# Tracksoar_v1_2_active_gps.net
KiCad netlist of a schematic drawn in EAGLE
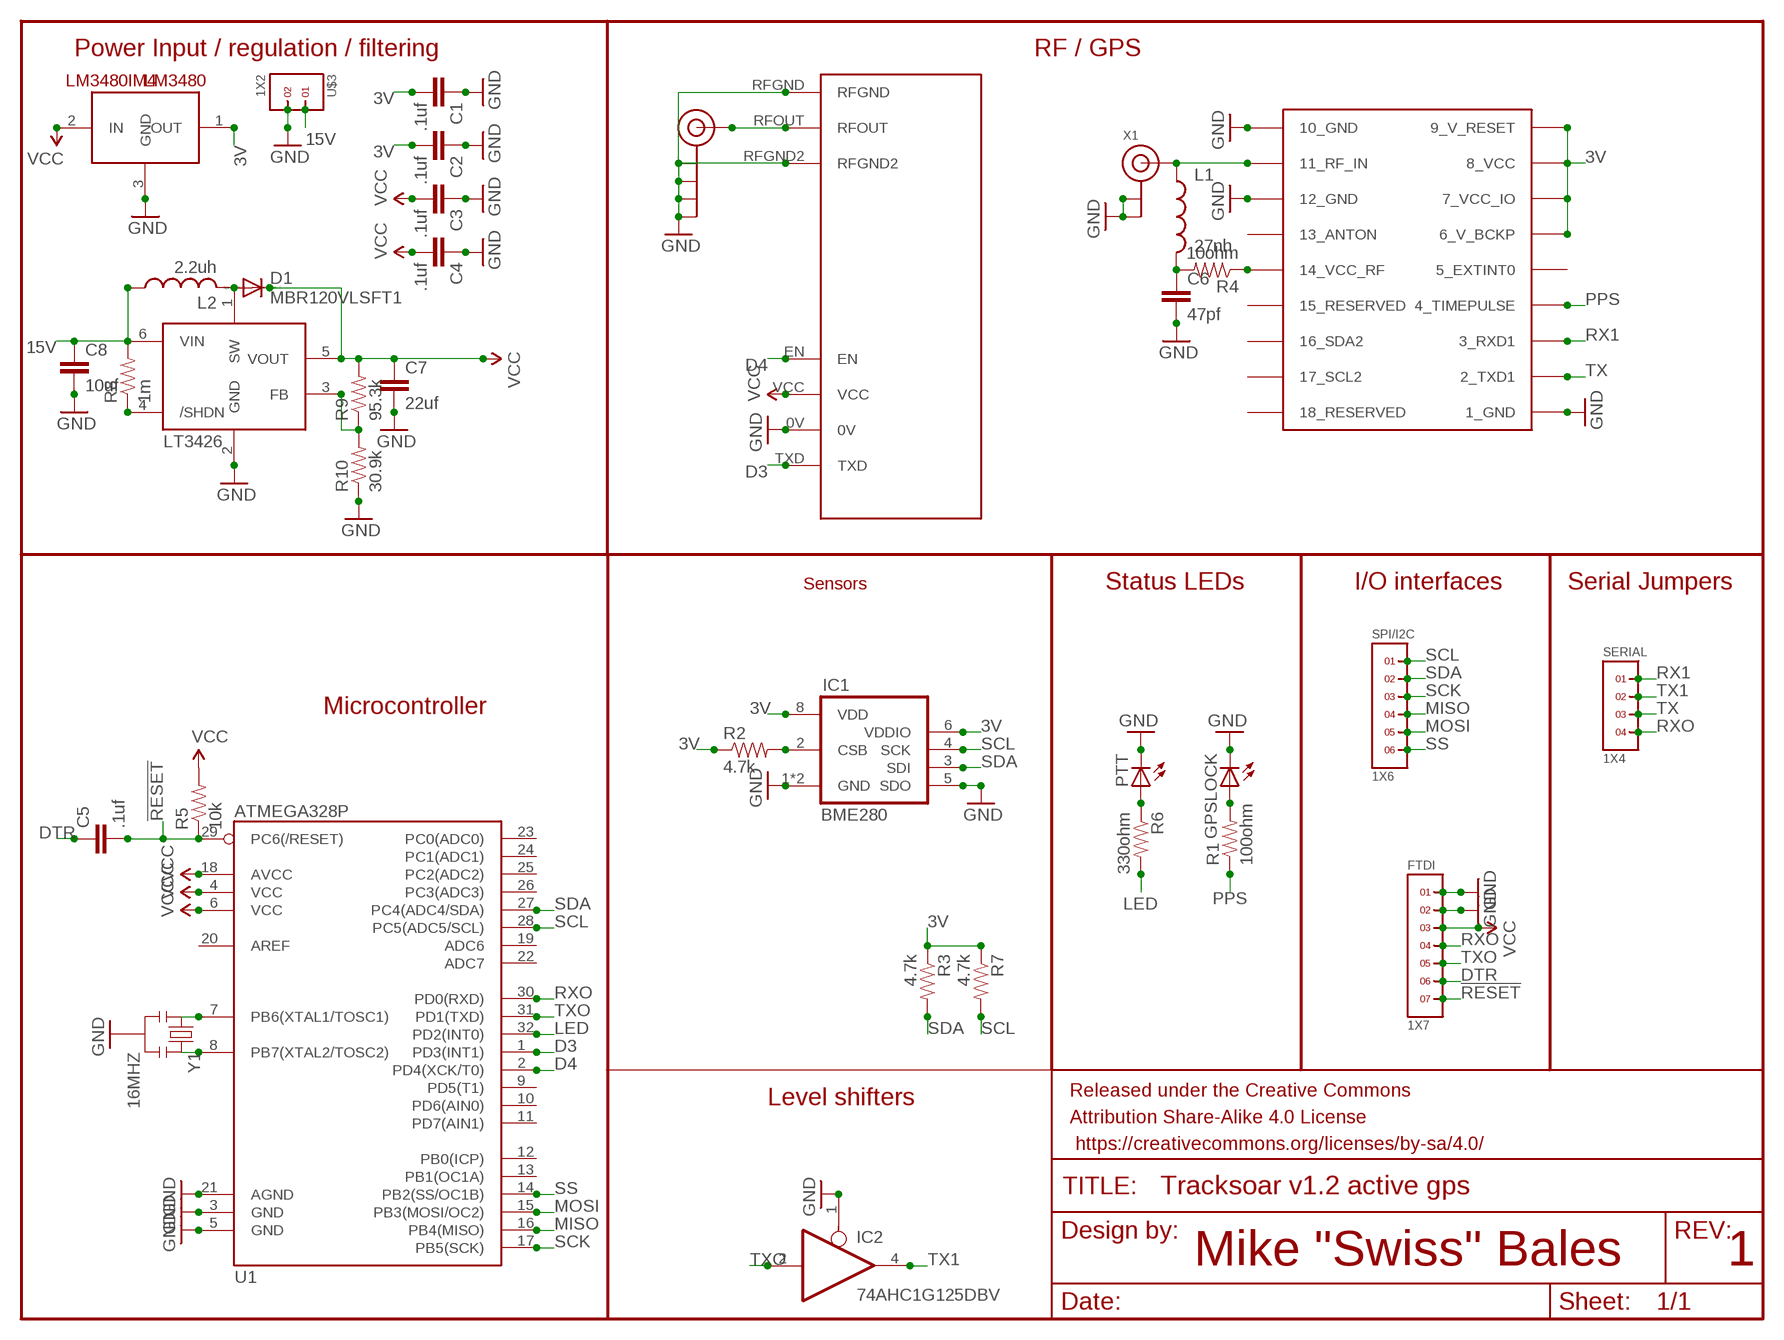
[diagram p0: schematic, sheet 1]

(export (version "E")
  (design (tool "Eeschema 10.0.6"))
  (components
    (comp (ref "C1")
      (value ".1uf")
      (footprint "eagle-import:0805")
      (libsource (lib "eagle-import") (part "CAP0805"))
    )
    (comp (ref "C2")
      (value ".1uf")
      (footprint "eagle-import:0805")
      (libsource (lib "eagle-import") (part "CAP0805"))
    )
    (comp (ref "C3")
      (value ".1uf")
      (footprint "eagle-import:0805")
      (libsource (lib "eagle-import") (part "CAP0805"))
    )
    (comp (ref "C4")
      (value ".1uf")
      (footprint "eagle-import:0805")
      (libsource (lib "eagle-import") (part "CAP0805"))
    )
    (comp (ref "C5")
      (value ".1uf")
      (footprint "eagle-import:0805")
      (libsource (lib "eagle-import") (part "CAP0805"))
    )
    (comp (ref "C6")
      (value "47pf")
      (footprint "eagle-import:0805")
      (libsource (lib "eagle-import") (part "SparkFun-Passives_CAP0805"))
    )
    (comp (ref "C7")
      (value "22uf")
      (footprint "eagle-import:0805")
      (libsource (lib "eagle-import") (part "CAP0805"))
    )
    (comp (ref "C8")
      (value "10uf")
      (footprint "eagle-import:0805")
      (libsource (lib "eagle-import") (part "CAP0805"))
    )
    (comp (ref "D1")
      (value "MBR120VLSFT1")
      (footprint "eagle-import:SOD123")
      (libsource (lib "eagle-import") (part "DIODE-SOD123"))
    )
    (comp (ref "FRAME1")
      (value "FRAME-LETTER")
      (footprint "eagle-import:CREATIVE_COMMONS")
      (libsource (lib "eagle-import") (part "FRAME-LETTER"))
    )
    (comp (ref "FTDI")
      (value "1X7")
      (footprint "eagle-import:1X7")
      (libsource (lib "eagle-import") (part "1X7"))
    )
    (comp (ref "GPSLOCK")
      (value "LEDCHIP-LED0805")
      (footprint "eagle-import:CHIP-LED0805")
      (libsource (lib "eagle-import") (part "LEDCHIP-LED0805"))
    )
    (comp (ref "IC1")
      (value "BME280")
      (footprint "eagle-import:BME280")
      (libsource (lib "eagle-import") (part "BME280"))
    )
    (comp (ref "IC2")
      (value "74AHC1G125DBV")
      (footprint "eagle-import:SOT23-5")
      (libsource (lib "eagle-import") (part "741G125DBVAHC"))
    )
    (comp (ref "J$1")
      (value "SMA_EDGE")
      (footprint "eagle-import:SMA-EDGE")
      (libsource (lib "eagle-import") (part "SMA_EDGE"))
    )
    (comp (ref "L1")
      (value "27nh")
      (footprint "eagle-import:0805")
      (libsource (lib "eagle-import") (part "INDUCTOR0805"))
    )
    (comp (ref "L2")
      (value "2.2uh")
      (footprint "eagle-import:L1812")
      (libsource (lib "eagle-import") (part "L-USL1812"))
    )
    (comp (ref "LM3480")
      (value "LM3480IM4")
      (footprint "eagle-import:SOT23-3")
      (libsource (lib "eagle-import") (part "LM3480IM4"))
    )
    (comp (ref "LT3426")
      (value "LT3426")
      (footprint "eagle-import:SOT23-6")
      (libsource (lib "eagle-import") (part "LT3426"))
    )
    (comp (ref "PTT")
      (value "LEDCHIP-LED0805")
      (footprint "eagle-import:CHIP-LED0805")
      (libsource (lib "eagle-import") (part "LEDCHIP-LED0805"))
    )
    (comp (ref "R1")
      (value "100ohm")
      (footprint "eagle-import:0805")
      (libsource (lib "eagle-import") (part "SparkFun-Resistors_RESISTOR0805-RES"))
    )
    (comp (ref "R2")
      (value "4.7k")
      (footprint "eagle-import:0805")
      (libsource (lib "eagle-import") (part "SparkFun-Resistors_RESISTOR0805-RES"))
    )
    (comp (ref "R3")
      (value "4.7k")
      (footprint "eagle-import:0805")
      (libsource (lib "eagle-import") (part "SparkFun-Resistors_RESISTOR0805-RES"))
    )
    (comp (ref "R4")
      (value "10ohm")
      (footprint "eagle-import:0805")
      (libsource (lib "eagle-import") (part "RESISTOR0805-RES"))
    )
    (comp (ref "R5")
      (value "10k")
      (footprint "eagle-import:0805")
      (libsource (lib "eagle-import") (part "SparkFun-Resistors_RESISTOR0805-RES"))
    )
    (comp (ref "R6")
      (value "330ohm")
      (footprint "eagle-import:0805")
      (libsource (lib "eagle-import") (part "SparkFun-Resistors_RESISTOR0805-RES"))
    )
    (comp (ref "R7")
      (value "4.7k")
      (footprint "eagle-import:0805")
      (libsource (lib "eagle-import") (part "SparkFun-Resistors_RESISTOR0805-RES"))
    )
    (comp (ref "R8")
      (value "1m")
      (footprint "eagle-import:0805")
      (libsource (lib "eagle-import") (part "SparkFun-Resistors_RESISTOR0805-RES"))
    )
    (comp (ref "R9")
      (value "95.3k")
      (footprint "eagle-import:0805")
      (libsource (lib "eagle-import") (part "SparkFun-Resistors_RESISTOR0805-RES"))
    )
    (comp (ref "R10")
      (value "30.9k")
      (footprint "eagle-import:0805")
      (libsource (lib "eagle-import") (part "SparkFun-Resistors_RESISTOR0805-RES"))
    )
    (comp (ref "SERIAL")
      (value "1X4")
      (footprint "eagle-import:1X4")
      (libsource (lib "eagle-import") (part "1X4"))
    )
    (comp (ref "SPI/I2C")
      (value "1X6")
      (footprint "eagle-import:1X6")
      (libsource (lib "eagle-import") (part "1X6"))
    )
    (comp (ref "U$1")
      (value "UBLOX_MAX")
      (footprint "eagle-import:UBLOX_MAX")
      (libsource (lib "eagle-import") (part "UBLOX_MAX"))
    )
    (comp (ref "U$2")
      (value "RADIOMETRIX-HX1")
      (footprint "eagle-import:RADIOMETRIX-HX1")
      (libsource (lib "eagle-import") (part "RADIOMETRIX-HX1"))
    )
    (comp (ref "U$3")
      (value "1X2")
      (footprint "eagle-import:1X2")
      (libsource (lib "eagle-import") (part "1X2"))
    )
    (comp (ref "U1")
      (value "ATMEGA328P")
      (footprint "eagle-import:MLF32")
      (libsource (lib "eagle-import") (part "ATMEGA168MLF"))
    )
    (comp (ref "X1")
      (value "ANTENNA_U.FL")
      (footprint "eagle-import:U.FL")
      (libsource (lib "eagle-import") (part "ANTENNA_U.FL"))
    )
    (comp (ref "Y1")
      (value "16MHZ")
      (footprint "eagle-import:RESONATOR-SMD")
      (libsource (lib "eagle-import") (part "RESONATOR16MHZ"))
    )
  )
  (nets
    (net (code "1") (name "/3V") (class "Default")
      (node (ref "C1") (pin "2") (pinfunction "2_2") (pintype "passive"))
      (node (ref "C2") (pin "2") (pinfunction "2_2") (pintype "passive"))
      (node (ref "IC1") (pin "6") (pinfunction "VDDIO_6") (pintype "power_in"))
      (node (ref "IC1") (pin "8") (pinfunction "VDD_8") (pintype "power_in"))
      (node (ref "LM3480") (pin "1") (pinfunction "OUT_1") (pintype "bidirectional"))
      (node (ref "R2") (pin "1") (pinfunction "1_1") (pintype "passive"))
      (node (ref "R3") (pin "1") (pinfunction "1_1") (pintype "passive"))
      (node (ref "R7") (pin "1") (pinfunction "1_1") (pintype "passive"))
      (node (ref "U$1") (pin "6_V_BCKP") (pinfunction "6_V_BCKP_6_V_BCKP") (pintype "bidirectional"))
      (node (ref "U$1") (pin "7_VCC_IO") (pinfunction "7_VCC_IO_7_VCC_IO") (pintype "power_in"))
      (node (ref "U$1") (pin "8_VCC") (pinfunction "8_VCC_8_VCC") (pintype "power_in"))
      (node (ref "U$1") (pin "9_V_RESET") (pinfunction "9_V_RESET_9_V_RESET") (pintype "power_in"))
    )
    (net (code "2") (name "/15V") (class "Default")
      (node (ref "C8") (pin "1") (pinfunction "1_1") (pintype "passive"))
      (node (ref "L2") (pin "1") (pinfunction "1_1") (pintype "passive"))
      (node (ref "LT3426") (pin "6") (pinfunction "VIN_6") (pintype "input"))
      (node (ref "R8") (pin "2") (pinfunction "2_2") (pintype "passive"))
      (node (ref "U$3") (pin "1") (pinfunction "1_1") (pintype "bidirectional"))
    )
    (net (code "3") (name "/D3") (class "Default")
      (node (ref "U$2") (pin "TXD") (pinfunction "TXD_TXD") (pintype "bidirectional"))
      (node (ref "U1") (pin "1") (pinfunction "PD3(INT1)_1") (pintype "bidirectional"))
    )
    (net (code "4") (name "/D4") (class "Default")
      (node (ref "U$2") (pin "EN") (pinfunction "EN_EN") (pintype "bidirectional"))
      (node (ref "U1") (pin "2") (pinfunction "PD4(XCK/T0)_2") (pintype "bidirectional"))
    )
    (net (code "5") (name "/DTR") (class "Default")
      (node (ref "C5") (pin "1") (pinfunction "1_1") (pintype "passive"))
      (node (ref "FTDI") (pin "6") (pinfunction "6_6") (pintype "bidirectional"))
    )
    (net (code "6") (name "/LED") (class "Default")
      (node (ref "R6") (pin "2") (pinfunction "2_2") (pintype "passive"))
      (node (ref "U1") (pin "32") (pinfunction "PD2(INT0)_32") (pintype "bidirectional"))
    )
    (net (code "7") (name "/MISO") (class "Default")
      (node (ref "SPI/I2C") (pin "4") (pinfunction "4_4") (pintype "bidirectional"))
      (node (ref "U1") (pin "16") (pinfunction "PB4(MISO)_16") (pintype "bidirectional"))
    )
    (net (code "8") (name "/MOSI") (class "Default")
      (node (ref "SPI/I2C") (pin "5") (pinfunction "5_5") (pintype "bidirectional"))
      (node (ref "U1") (pin "15") (pinfunction "PB3(MOSI/OC2)_15") (pintype "bidirectional"))
    )
    (net (code "9") (name "/PPS") (class "Default")
      (node (ref "R1") (pin "1") (pinfunction "1_1") (pintype "passive"))
      (node (ref "U$1") (pin "4_TIMEPULSE") (pinfunction "4_TIMEPULSE_4_TIMEPULSE") (pintype "bidirectional"))
    )
    (net (code "10") (name "/RX1") (class "Default")
      (node (ref "SERIAL") (pin "1") (pinfunction "1_1") (pintype "bidirectional"))
      (node (ref "U$1") (pin "3_RXD1") (pinfunction "3_RXD1_3_RXD1") (pintype "bidirectional"))
    )
    (net (code "11") (name "/RXO") (class "Default")
      (node (ref "FTDI") (pin "4") (pinfunction "4_4") (pintype "bidirectional"))
      (node (ref "SERIAL") (pin "4") (pinfunction "4_4") (pintype "bidirectional"))
      (node (ref "U1") (pin "30") (pinfunction "PD0(RXD)_30") (pintype "bidirectional"))
    )
    (net (code "12") (name "/SCK") (class "Default")
      (node (ref "SPI/I2C") (pin "3") (pinfunction "3_3") (pintype "bidirectional"))
      (node (ref "U1") (pin "17") (pinfunction "PB5(SCK)_17") (pintype "bidirectional"))
    )
    (net (code "13") (name "/SCL") (class "Default")
      (node (ref "IC1") (pin "4") (pinfunction "SCK_4") (pintype "bidirectional"))
      (node (ref "R7") (pin "2") (pinfunction "2_2") (pintype "passive"))
      (node (ref "SPI/I2C") (pin "1") (pinfunction "1_1") (pintype "bidirectional"))
      (node (ref "U1") (pin "28") (pinfunction "PC5(ADC5/SCL)_28") (pintype "bidirectional"))
    )
    (net (code "14") (name "/SDA") (class "Default")
      (node (ref "IC1") (pin "3") (pinfunction "SDI_3") (pintype "bidirectional"))
      (node (ref "R3") (pin "2") (pinfunction "2_2") (pintype "passive"))
      (node (ref "SPI/I2C") (pin "2") (pinfunction "2_2") (pintype "bidirectional"))
      (node (ref "U1") (pin "27") (pinfunction "PC4(ADC4/SDA)_27") (pintype "bidirectional"))
    )
    (net (code "15") (name "/SS") (class "Default")
      (node (ref "SPI/I2C") (pin "6") (pinfunction "6_6") (pintype "bidirectional"))
      (node (ref "U1") (pin "14") (pinfunction "PB2(SS/OC1B)_14") (pintype "bidirectional"))
    )
    (net (code "16") (name "/TX") (class "Default")
      (node (ref "SERIAL") (pin "3") (pinfunction "3_3") (pintype "bidirectional"))
      (node (ref "U$1") (pin "2_TXD1") (pinfunction "2_TXD1_2_TXD1") (pintype "bidirectional"))
    )
    (net (code "17") (name "/TX1") (class "Default")
      (node (ref "IC2") (pin "4") (pinfunction "O_4") (pintype "tri_state"))
      (node (ref "SERIAL") (pin "2") (pinfunction "2_2") (pintype "bidirectional"))
    )
    (net (code "18") (name "/TXO") (class "Default")
      (node (ref "FTDI") (pin "5") (pinfunction "5_5") (pintype "bidirectional"))
      (node (ref "IC2") (pin "2") (pinfunction "I_2") (pintype "input"))
      (node (ref "U1") (pin "31") (pinfunction "PD1(TXD)_31") (pintype "bidirectional"))
    )
    (net (code "19") (name "/~{RESET}") (class "Default")
      (node (ref "C5") (pin "2") (pinfunction "2_2") (pintype "passive"))
      (node (ref "FTDI") (pin "7") (pinfunction "7_7") (pintype "bidirectional"))
      (node (ref "R5") (pin "1") (pinfunction "1_1") (pintype "passive"))
      (node (ref "U1") (pin "29") (pinfunction "PC6(/RESET)_29") (pintype "bidirectional"))
    )
    (net (code "20") (name "GND") (class "Default")
      (node (ref "C1") (pin "1") (pinfunction "1_1") (pintype "passive"))
      (node (ref "C2") (pin "1") (pinfunction "1_1") (pintype "passive"))
      (node (ref "C3") (pin "1") (pinfunction "1_1") (pintype "passive"))
      (node (ref "C4") (pin "1") (pinfunction "1_1") (pintype "passive"))
      (node (ref "C6") (pin "2") (pinfunction "2_2") (pintype "passive"))
      (node (ref "C7") (pin "2") (pinfunction "2_2") (pintype "passive"))
      (node (ref "C8") (pin "2") (pinfunction "2_2") (pintype "passive"))
      (node (ref "FTDI") (pin "1") (pinfunction "1_1") (pintype "bidirectional"))
      (node (ref "FTDI") (pin "2") (pinfunction "2_2") (pintype "bidirectional"))
      (node (ref "GPSLOCK") (pin "C") (pinfunction "C_C") (pintype "passive"))
      (node (ref "IC1") (pin "1") (pinfunction "GND_1") (pintype "power_in"))
      (node (ref "IC1") (pin "5") (pinfunction "SDO_5") (pintype "input"))
      (node (ref "IC1") (pin "7") (pinfunction "GND_7") (pintype "power_in"))
      (node (ref "IC2") (pin "1") (pinfunction "OE_1") (pintype "input"))
      (node (ref "J$1") (pin "GND@0") (pinfunction "GND_GND@0") (pintype "bidirectional"))
      (node (ref "J$1") (pin "GND@1") (pinfunction "GND_GND@1") (pintype "bidirectional"))
      (node (ref "J$1") (pin "GND@2") (pinfunction "GND_GND@2") (pintype "bidirectional"))
      (node (ref "J$1") (pin "GND@3") (pinfunction "GND_GND@3") (pintype "bidirectional"))
      (node (ref "LM3480") (pin "3") (pinfunction "GND_3") (pintype "bidirectional"))
      (node (ref "LT3426") (pin "2") (pinfunction "GND_2") (pintype "power_in"))
      (node (ref "PTT") (pin "C") (pinfunction "C_C") (pintype "passive"))
      (node (ref "R10") (pin "1") (pinfunction "1_1") (pintype "passive"))
      (node (ref "U$1") (pin "10_GND") (pinfunction "10_GND_10_GND") (pintype "power_in"))
      (node (ref "U$1") (pin "12_GND") (pinfunction "12_GND_12_GND") (pintype "power_in"))
      (node (ref "U$1") (pin "1_GND") (pinfunction "1_GND_1_GND") (pintype "power_in"))
      (node (ref "U$2") (pin "0V") (pinfunction "0V_0V") (pintype "bidirectional"))
      (node (ref "U$2") (pin "RFGND") (pinfunction "RFGND_RFGND") (pintype "bidirectional"))
      (node (ref "U$2") (pin "RFGND2") (pinfunction "RFGND2_RFGND2") (pintype "bidirectional"))
      (node (ref "U$3") (pin "2") (pinfunction "2_2") (pintype "bidirectional"))
      (node (ref "U1") (pin "21") (pinfunction "AGND_21") (pintype "bidirectional"))
      (node (ref "U1") (pin "3") (pinfunction "GND_3") (pintype "bidirectional"))
      (node (ref "U1") (pin "5") (pinfunction "GND_5") (pintype "bidirectional"))
      (node (ref "X1") (pin "1") (pinfunction "GND_1") (pintype "passive"))
      (node (ref "X1") (pin "2") (pinfunction "GND_2") (pintype "passive"))
      (node (ref "Y1") (pin "2") (pinfunction "2_2") (pintype "passive"))
    )
    (net (code "21") (name "Net-(C6-Pad1)") (class "Default")
      (node (ref "C6") (pin "1") (pinfunction "1_1") (pintype "passive"))
      (node (ref "L1") (pin "2") (pinfunction "2_2") (pintype "passive"))
      (node (ref "R4") (pin "2") (pinfunction "2_2") (pintype "passive"))
    )
    (net (code "22") (name "Net-(GPSLOCK-PadA)") (class "Default")
      (node (ref "GPSLOCK") (pin "A") (pinfunction "A_A") (pintype "passive"))
      (node (ref "R1") (pin "2") (pinfunction "2_2") (pintype "passive"))
    )
    (net (code "23") (name "Net-(IC1-CSB)") (class "Default")
      (node (ref "IC1") (pin "2") (pinfunction "CSB_2") (pintype "input"))
      (node (ref "R2") (pin "2") (pinfunction "2_2") (pintype "passive"))
    )
    (net (code "24") (name "Net-(J$1-SIGNAL)") (class "Default")
      (node (ref "J$1") (pin "SIG") (pinfunction "SIGNAL_SIG") (pintype "bidirectional"))
      (node (ref "U$2") (pin "RFOUT") (pinfunction "RFOUT_RFOUT") (pintype "bidirectional"))
    )
    (net (code "25") (name "Net-(LT3426-FB)") (class "Default")
      (node (ref "LT3426") (pin "3") (pinfunction "FB_3") (pintype "input"))
      (node (ref "R10") (pin "2") (pinfunction "2_2") (pintype "passive"))
      (node (ref "R9") (pin "1") (pinfunction "1_1") (pintype "passive"))
    )
    (net (code "26") (name "Net-(LT3426-SW)") (class "Default")
      (node (ref "D1") (pin "A") (pinfunction "A_A") (pintype "passive"))
      (node (ref "L2") (pin "2") (pinfunction "2_2") (pintype "passive"))
      (node (ref "LT3426") (pin "1") (pinfunction "SW_1") (pintype "output"))
    )
    (net (code "27") (name "Net-(LT3426-{slash}SHDN)") (class "Default")
      (node (ref "LT3426") (pin "4") (pinfunction "/SHDN_4") (pintype "input"))
      (node (ref "R8") (pin "1") (pinfunction "1_1") (pintype "passive"))
    )
    (net (code "28") (name "Net-(PTT-PadA)") (class "Default")
      (node (ref "PTT") (pin "A") (pinfunction "A_A") (pintype "passive"))
      (node (ref "R6") (pin "1") (pinfunction "1_1") (pintype "passive"))
    )
    (net (code "29") (name "Net-(R4-Pad1)") (class "Default")
      (node (ref "R4") (pin "1") (pinfunction "1_1") (pintype "passive"))
      (node (ref "U$1") (pin "14_VCC_RF") (pinfunction "14_VCC_RF_14_VCC_RF") (pintype "bidirectional"))
    )
    (net (code "30") (name "Net-(U1-PB6(XTAL1{slash}TOSC1))") (class "Default")
      (node (ref "U1") (pin "7") (pinfunction "PB6(XTAL1/TOSC1)_7") (pintype "bidirectional"))
      (node (ref "Y1") (pin "1") (pinfunction "1_1") (pintype "passive"))
    )
    (net (code "31") (name "Net-(U1-PB7(XTAL2{slash}TOSC2))") (class "Default")
      (node (ref "U1") (pin "8") (pinfunction "PB7(XTAL2/TOSC2)_8") (pintype "bidirectional"))
      (node (ref "Y1") (pin "3") (pinfunction "3_3") (pintype "passive"))
    )
    (net (code "32") (name "Net-(X1-SIGNAL)") (class "Default")
      (node (ref "L1") (pin "1") (pinfunction "1_1") (pintype "passive"))
      (node (ref "U$1") (pin "11_RF_IN") (pinfunction "11_RF_IN_11_RF_IN") (pintype "bidirectional"))
      (node (ref "X1") (pin "3") (pinfunction "SIGNAL_3") (pintype "passive"))
    )
    (net (code "33") (name "VCC") (class "Default")
      (node (ref "C3") (pin "2") (pinfunction "2_2") (pintype "passive"))
      (node (ref "C4") (pin "2") (pinfunction "2_2") (pintype "passive"))
      (node (ref "C7") (pin "1") (pinfunction "1_1") (pintype "passive"))
      (node (ref "D1") (pin "C") (pinfunction "C_C") (pintype "passive"))
      (node (ref "FTDI") (pin "3") (pinfunction "3_3") (pintype "bidirectional"))
      (node (ref "LM3480") (pin "2") (pinfunction "IN_2") (pintype "bidirectional"))
      (node (ref "LT3426") (pin "5") (pinfunction "VOUT_5") (pintype "output"))
      (node (ref "R5") (pin "2") (pinfunction "2_2") (pintype "passive"))
      (node (ref "R9") (pin "2") (pinfunction "2_2") (pintype "passive"))
      (node (ref "U$2") (pin "VCC") (pinfunction "VCC_VCC") (pintype "bidirectional"))
      (node (ref "U1") (pin "18") (pinfunction "AVCC_18") (pintype "bidirectional"))
      (node (ref "U1") (pin "4") (pinfunction "VCC_4") (pintype "bidirectional"))
      (node (ref "U1") (pin "6") (pinfunction "VCC_6") (pintype "bidirectional"))
    )
    (net (code "34") (name "unconnected-(U$1-Pad5_EXTINT0)") (class "Default")
      (node (ref "U$1") (pin "5_EXTINT0") (pinfunction "5_EXTINT0_5_EXTINT0") (pintype "bidirectional"))
    )
    (net (code "35") (name "unconnected-(U$1-Pad13_ANTON)") (class "Default")
      (node (ref "U$1") (pin "13_ANTON") (pinfunction "13_ANTON_13_ANTON") (pintype "bidirectional"))
    )
    (net (code "36") (name "unconnected-(U$1-Pad15_RESERVED)") (class "Default")
      (node (ref "U$1") (pin "15_RESERVED") (pinfunction "15_RESERVED_15_RESERVED") (pintype "bidirectional"))
    )
    (net (code "37") (name "unconnected-(U$1-Pad16_SDA2)") (class "Default")
      (node (ref "U$1") (pin "16_SDA2") (pinfunction "16_SDA2_16_SDA2") (pintype "bidirectional"))
    )
    (net (code "38") (name "unconnected-(U$1-Pad17_SCL2)") (class "Default")
      (node (ref "U$1") (pin "17_SCL2") (pinfunction "17_SCL2_17_SCL2") (pintype "bidirectional"))
    )
    (net (code "39") (name "unconnected-(U$1-Pad18_RESERVED)") (class "Default")
      (node (ref "U$1") (pin "18_RESERVED") (pinfunction "18_RESERVED_18_RESERVED") (pintype "bidirectional"))
    )
    (net (code "40") (name "unconnected-(U1-ADC6-Pad19)") (class "Default")
      (node (ref "U1") (pin "19") (pinfunction "ADC6_19") (pintype "bidirectional"))
    )
    (net (code "41") (name "unconnected-(U1-ADC7-Pad22)") (class "Default")
      (node (ref "U1") (pin "22") (pinfunction "ADC7_22") (pintype "bidirectional"))
    )
    (net (code "42") (name "unconnected-(U1-AREF-Pad20)") (class "Default")
      (node (ref "U1") (pin "20") (pinfunction "AREF_20") (pintype "bidirectional"))
    )
    (net (code "43") (name "unconnected-(U1-PB0(ICP)-Pad12)") (class "Default")
      (node (ref "U1") (pin "12") (pinfunction "PB0(ICP)_12") (pintype "bidirectional"))
    )
    (net (code "44") (name "unconnected-(U1-PB1(OC1A)-Pad13)") (class "Default")
      (node (ref "U1") (pin "13") (pinfunction "PB1(OC1A)_13") (pintype "bidirectional"))
    )
    (net (code "45") (name "unconnected-(U1-PC0(ADC0)-Pad23)") (class "Default")
      (node (ref "U1") (pin "23") (pinfunction "PC0(ADC0)_23") (pintype "bidirectional"))
    )
    (net (code "46") (name "unconnected-(U1-PC1(ADC1)-Pad24)") (class "Default")
      (node (ref "U1") (pin "24") (pinfunction "PC1(ADC1)_24") (pintype "bidirectional"))
    )
    (net (code "47") (name "unconnected-(U1-PC2(ADC2)-Pad25)") (class "Default")
      (node (ref "U1") (pin "25") (pinfunction "PC2(ADC2)_25") (pintype "bidirectional"))
    )
    (net (code "48") (name "unconnected-(U1-PC3(ADC3)-Pad26)") (class "Default")
      (node (ref "U1") (pin "26") (pinfunction "PC3(ADC3)_26") (pintype "bidirectional"))
    )
    (net (code "49") (name "unconnected-(U1-PD5(T1)-Pad9)") (class "Default")
      (node (ref "U1") (pin "9") (pinfunction "PD5(T1)_9") (pintype "bidirectional"))
    )
    (net (code "50") (name "unconnected-(U1-PD6(AIN0)-Pad10)") (class "Default")
      (node (ref "U1") (pin "10") (pinfunction "PD6(AIN0)_10") (pintype "bidirectional"))
    )
    (net (code "51") (name "unconnected-(U1-PD7(AIN1)-Pad11)") (class "Default")
      (node (ref "U1") (pin "11") (pinfunction "PD7(AIN1)_11") (pintype "bidirectional"))
    )
  )
)
